# Sheet1.net
KiCad netlist of a schematic drawn in Altium Designer
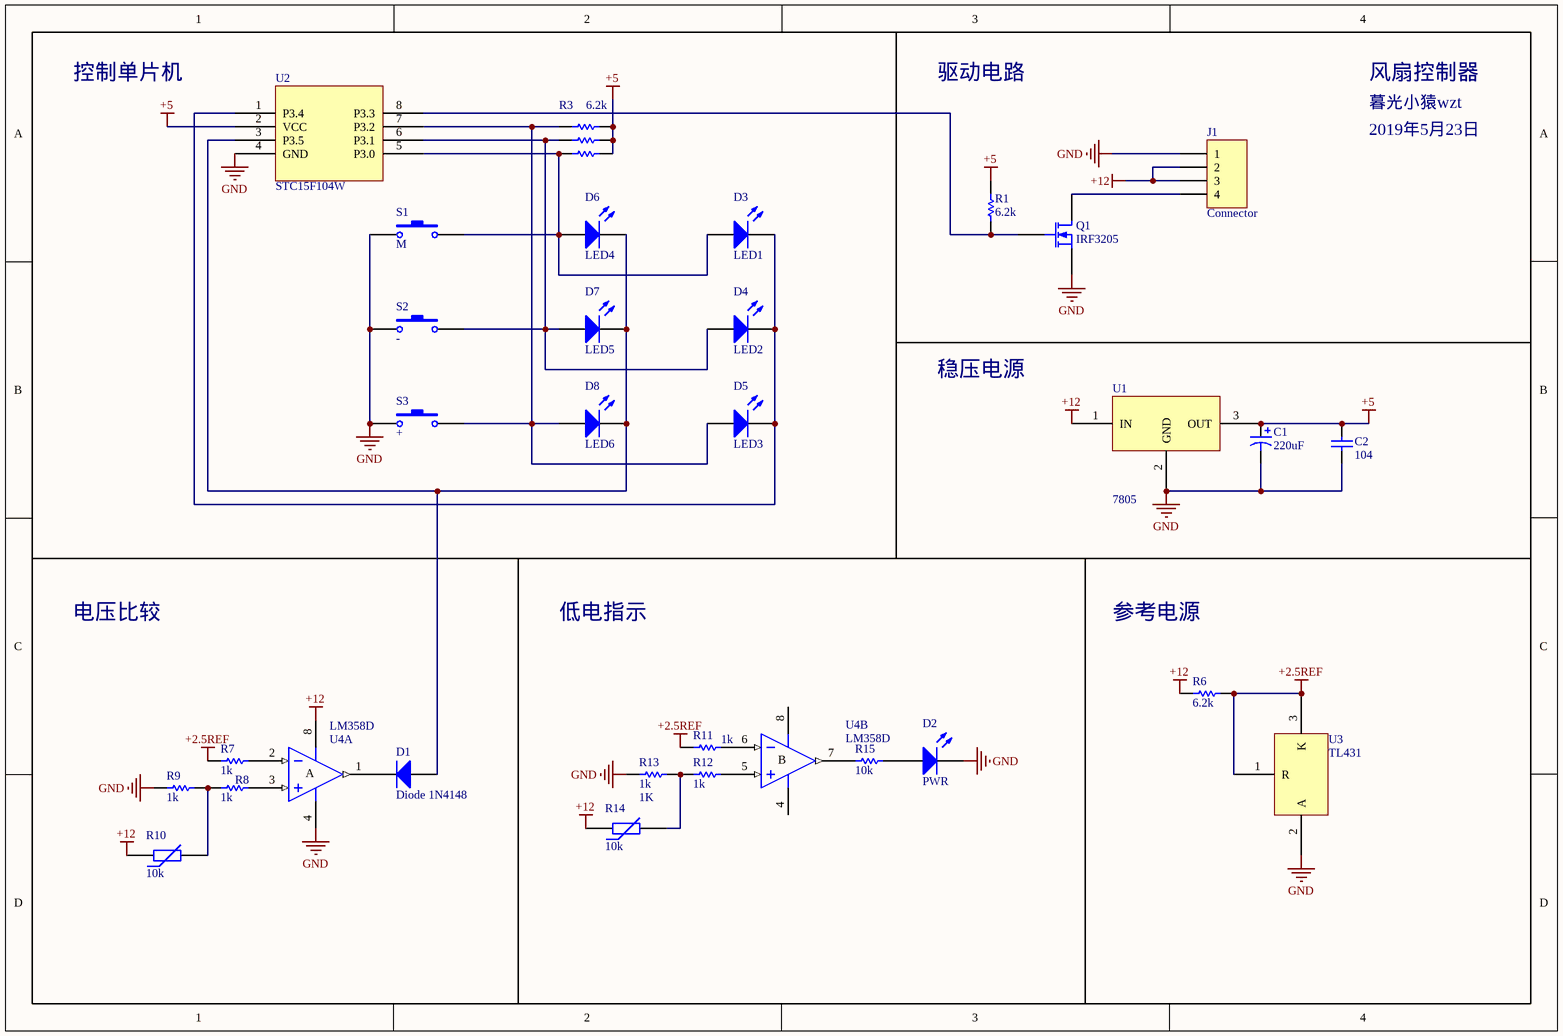
[diagram p0: Sheet1.SchDoc]

(export (version "E")
  (design (tool "Eeschema 10.0.6"))
  (components
    (comp (ref "C1")
      (value "220uF")
      (footprint "RB7.6-15")
      (description "Polarized Capacitor (Radial)")
      (fields (field (name "PUBLISHER") "Altium Limited"))
      (libsource (lib "Miscellaneous Devices") (part "Cap Pol1"))
    )
    (comp (ref "C2")
      (value "104")
      (footprint "RAD-0.3")
      (description "Capacitor")
      (fields (field (name "PUBLISHER") "Altium Limited"))
      (libsource (lib "Miscellaneous Devices") (part "Cap"))
    )
    (comp (ref "D1")
      (value "Diode 1N4148")
      (footprint "DO-35")
      (description "High Conductance Fast Diode")
      (fields (field (name "PUBLISHER") "Altium Limited"))
      (libsource (lib "Miscellaneous Devices") (part "Diode 1N4148"))
    )
    (comp (ref "D2")
      (value "PWR")
      (footprint "LED-0")
      (description "Typical INFRARED GaAs LED")
      (fields (field (name "PUBLISHER") "Altium Limited"))
      (libsource (lib "Miscellaneous Devices") (part "LED0"))
    )
    (comp (ref "D3")
      (value "LED1")
      (footprint "LED-0")
      (description "Typical INFRARED GaAs LED")
      (fields (field (name "PUBLISHER") "Altium Limited"))
      (libsource (lib "Miscellaneous Devices") (part "LED0"))
    )
    (comp (ref "D4")
      (value "LED2")
      (footprint "LED-0")
      (description "Typical INFRARED GaAs LED")
      (fields (field (name "PUBLISHER") "Altium Limited"))
      (libsource (lib "Miscellaneous Devices") (part "LED0"))
    )
    (comp (ref "D5")
      (value "LED3")
      (footprint "LED-0")
      (description "Typical INFRARED GaAs LED")
      (fields (field (name "PUBLISHER") "Altium Limited"))
      (libsource (lib "Miscellaneous Devices") (part "LED0"))
    )
    (comp (ref "D6")
      (value "LED4")
      (footprint "LED-0")
      (description "Typical INFRARED GaAs LED")
      (fields (field (name "PUBLISHER") "Altium Limited"))
      (libsource (lib "Miscellaneous Devices") (part "LED0"))
    )
    (comp (ref "D7")
      (value "LED5")
      (footprint "LED-0")
      (description "Typical INFRARED GaAs LED")
      (fields (field (name "PUBLISHER") "Altium Limited"))
      (libsource (lib "Miscellaneous Devices") (part "LED0"))
    )
    (comp (ref "D8")
      (value "LED6")
      (footprint "LED-0")
      (description "Typical INFRARED GaAs LED")
      (fields (field (name "PUBLISHER") "Altium Limited"))
      (libsource (lib "Miscellaneous Devices") (part "LED0"))
    )
    (comp (ref "J1")
      (value "Connector")
      (footprint "HDR1X4")
      (description "Header, 4-Pin")
      (fields (field (name "PUBLISHER") "Altium Limited"))
      (libsource (lib "Miscellaneous Connectors") (part "Header 4"))
    )
    (comp (ref "Q1")
      (value "IRF3205")
      (footprint "E3")
      (description "N-Channel MOSFET")
      (fields (field (name "PUBLISHER") "Altium Limited"))
      (libsource (lib "Miscellaneous Devices") (part "MOSFET-N"))
    )
    (comp (ref "R1")
      (value "6.2k")
      (footprint "AXIAL-0.3")
      (description "Resistor")
      (fields (field (name "PUBLISHER") "Altium Limited"))
      (libsource (lib "Miscellaneous Devices") (part "Res1"))
    )
    (comp (ref "R3")
      (value "6.2k")
      (footprint "AXIAL-0.3")
      (description "Resistor")
      (fields (field (name "PUBLISHER") "Altium Limited"))
      (libsource (lib "Miscellaneous Devices") (part "Res1"))
    )
    (comp (ref "R4")
      (value "6.2k")
      (footprint "AXIAL-0.3")
      (description "Resistor")
      (fields (field (name "PUBLISHER") "Altium Limited"))
      (libsource (lib "Miscellaneous Devices") (part "Res1"))
    )
    (comp (ref "R5")
      (value "6.2k")
      (footprint "AXIAL-0.3")
      (description "Resistor")
      (fields (field (name "PUBLISHER") "Altium Limited"))
      (libsource (lib "Miscellaneous Devices") (part "Res1"))
    )
    (comp (ref "R6")
      (value "6.2k")
      (footprint "AXIAL-0.3")
      (description "Resistor")
      (fields (field (name "PUBLISHER") "Altium Limited"))
      (libsource (lib "Miscellaneous Devices") (part "Res1"))
    )
    (comp (ref "R7")
      (value "1k")
      (footprint "AXIAL-0.3")
      (description "Resistor")
      (fields (field (name "PUBLISHER") "Altium Limited"))
      (libsource (lib "Miscellaneous Devices") (part "Res1"))
    )
    (comp (ref "R8")
      (value "1k")
      (footprint "AXIAL-0.3")
      (description "Resistor")
      (fields (field (name "PUBLISHER") "Altium Limited"))
      (libsource (lib "Miscellaneous Devices") (part "Res1"))
    )
    (comp (ref "R9")
      (value "1k")
      (footprint "AXIAL-0.3")
      (description "Resistor")
      (fields (field (name "PUBLISHER") "Altium Limited"))
      (libsource (lib "Miscellaneous Devices") (part "Res1"))
    )
    (comp (ref "R10")
      (value "10k")
      (footprint "6-0805_N")
      (description "Varistor (Voltage-Sensitive Resistor)")
      (fields (field (name "PUBLISHER") "Altium Limited"))
      (libsource (lib "Miscellaneous Devices") (part "Res Varistor"))
    )
    (comp (ref "R11")
      (value "1k")
      (footprint "AXIAL-0.3")
      (description "Resistor")
      (fields (field (name "PUBLISHER") "Altium Limited"))
      (libsource (lib "Miscellaneous Devices") (part "Res1"))
    )
    (comp (ref "R12")
      (value "1k")
      (footprint "AXIAL-0.3")
      (description "Resistor")
      (fields (field (name "PUBLISHER") "Altium Limited"))
      (libsource (lib "Miscellaneous Devices") (part "Res1"))
    )
    (comp (ref "R13")
      (value "1k")
      (footprint "AXIAL-0.3")
      (description "Resistor")
      (fields (field (name "ALTIUM_VALUE") "1K") (field (name "PUBLISHER") "Altium Limited"))
      (libsource (lib "Miscellaneous Devices") (part "Res1"))
    )
    (comp (ref "R14")
      (value "10k")
      (footprint "6-0805_N")
      (description "Varistor (Voltage-Sensitive Resistor)")
      (fields (field (name "PUBLISHER") "Altium Limited"))
      (libsource (lib "Miscellaneous Devices") (part "Res Varistor"))
    )
    (comp (ref "R15")
      (value "10k")
      (footprint "AXIAL-0.3")
      (description "Resistor")
      (fields (field (name "PUBLISHER") "Altium Limited"))
      (libsource (lib "Miscellaneous Devices") (part "Res1"))
    )
    (comp (ref "S1")
      (value "M")
      (footprint "SPST-2")
      (description "Switch")
      (fields (field (name "PUBLISHER") "Altium Limited"))
      (libsource (lib "Miscellaneous Devices") (part "SW-PB"))
    )
    (comp (ref "S2")
      (value "-")
      (footprint "SPST-2")
      (description "Switch")
      (fields (field (name "PUBLISHER") "Altium Limited"))
      (libsource (lib "Miscellaneous Devices") (part "SW-PB"))
    )
    (comp (ref "S3")
      (value "+")
      (footprint "SPST-2")
      (description "Switch")
      (fields (field (name "PUBLISHER") "Altium Limited"))
      (libsource (lib "Miscellaneous Devices") (part "SW-PB"))
    )
    (comp (ref "U1") (value "7805") (libsource (lib "Schlib1") (part "7805")))
    (comp (ref "U2") (value "STC15F104W") (libsource (lib "Schlib1") (part "STC15F104W")))
    (comp (ref "U3") (value "TL431") (libsource (lib "Schlib1") (part "TL431")))
    (comp (ref "U4")
      (value "LM358D")
      (footprint "D008_L")
      (description "Dual Operational Amplifier")
      (fields (field (name "PUBLISHER") "Altium Limited"))
      (libsource (lib "TI Operational Amplifier") (part "LM358D"))
    )
  )
  (nets
    (net (code "1") (name "+2.5REF") (class "Default")
      (node (ref "R11") (pin "1") (pinfunction "1_1") (pintype "passive"))
      (node (ref "R6") (pin "2") (pinfunction "2_2") (pintype "passive"))
      (node (ref "R7") (pin "1") (pinfunction "1_1") (pintype "passive"))
      (node (ref "U3") (pin "1") (pinfunction "R_1") (pintype "passive"))
      (node (ref "U3") (pin "3") (pinfunction "K_3") (pintype "passive"))
    )
    (net (code "2") (name "+5") (class "Default")
      (node (ref "C1") (pin "1") (pinfunction "1_1") (pintype "passive"))
      (node (ref "C2") (pin "2") (pinfunction "2_2") (pintype "passive"))
      (node (ref "R1") (pin "2") (pinfunction "2_2") (pintype "passive"))
      (node (ref "R3") (pin "2") (pinfunction "2_2") (pintype "passive"))
      (node (ref "R4") (pin "2") (pinfunction "2_2") (pintype "passive"))
      (node (ref "R5") (pin "2") (pinfunction "2_2") (pintype "passive"))
      (node (ref "U1") (pin "3") (pinfunction "OUT_3") (pintype "passive"))
      (node (ref "U2") (pin "2") (pinfunction "VCC_2") (pintype "passive"))
    )
    (net (code "3") (name "+12") (class "Default")
      (node (ref "J1") (pin "2") (pinfunction "2_2") (pintype "passive"))
      (node (ref "J1") (pin "3") (pinfunction "3_3") (pintype "passive"))
      (node (ref "R10") (pin "1") (pinfunction "1_1") (pintype "passive"))
      (node (ref "R14") (pin "1") (pinfunction "1_1") (pintype "passive"))
      (node (ref "R6") (pin "1") (pinfunction "1_1") (pintype "passive"))
      (node (ref "U1") (pin "1") (pinfunction "IN_1") (pintype "passive"))
      (node (ref "U4") (pin "8") (pinfunction "V+_8") (pintype "power_in"))
    )
    (net (code "4") (name "GND") (class "Default")
      (node (ref "C1") (pin "2") (pinfunction "2_2") (pintype "passive"))
      (node (ref "C2") (pin "1") (pinfunction "1_1") (pintype "passive"))
      (node (ref "D2") (pin "2") (pinfunction "K_2") (pintype "passive"))
      (node (ref "J1") (pin "1") (pinfunction "1_1") (pintype "passive"))
      (node (ref "Q1") (pin "3") (pinfunction "S_3") (pintype "passive"))
      (node (ref "R13") (pin "1") (pinfunction "1_1") (pintype "passive"))
      (node (ref "R9") (pin "1") (pinfunction "1_1") (pintype "passive"))
      (node (ref "S1") (pin "1") (pinfunction "1_1") (pintype "passive"))
      (node (ref "S2") (pin "1") (pinfunction "1_1") (pintype "passive"))
      (node (ref "S3") (pin "1") (pinfunction "1_1") (pintype "passive"))
      (node (ref "U1") (pin "2") (pinfunction "GND_2") (pintype "passive"))
      (node (ref "U2") (pin "4") (pinfunction "GND_4") (pintype "passive"))
      (node (ref "U3") (pin "2") (pinfunction "A_2") (pintype "passive"))
      (node (ref "U4") (pin "4") (pinfunction "V-_4") (pintype "power_in"))
    )
    (net (code "5") (name "Net-(D1-A)") (class "Default")
      (node (ref "D1") (pin "1") (pinfunction "A_1") (pintype "passive"))
      (node (ref "D6") (pin "2") (pinfunction "K_2") (pintype "passive"))
      (node (ref "D7") (pin "2") (pinfunction "K_2") (pintype "passive"))
      (node (ref "D8") (pin "2") (pinfunction "K_2") (pintype "passive"))
      (node (ref "U2") (pin "3") (pinfunction "P3.5_3") (pintype "passive"))
    )
    (net (code "6") (name "Net-(D1-K)") (class "Default")
      (node (ref "D1") (pin "2") (pinfunction "K_2") (pintype "passive"))
      (node (ref "U4") (pin "1") (pinfunction "OUT_1") (pintype "output"))
    )
    (net (code "7") (name "Net-(D2-A)") (class "Default")
      (node (ref "D2") (pin "1") (pinfunction "A_1") (pintype "passive"))
      (node (ref "R15") (pin "2") (pinfunction "2_2") (pintype "passive"))
    )
    (net (code "8") (name "Net-(D3-A)") (class "Default")
      (node (ref "D3") (pin "1") (pinfunction "A_1") (pintype "passive"))
      (node (ref "D6") (pin "1") (pinfunction "A_1") (pintype "passive"))
      (node (ref "R5") (pin "1") (pinfunction "1_1") (pintype "passive"))
      (node (ref "S1") (pin "2") (pinfunction "2_2") (pintype "passive"))
      (node (ref "U2") (pin "5") (pinfunction "P3.0_5") (pintype "passive"))
    )
    (net (code "9") (name "Net-(D3-K)") (class "Default")
      (node (ref "D3") (pin "2") (pinfunction "K_2") (pintype "passive"))
      (node (ref "D4") (pin "2") (pinfunction "K_2") (pintype "passive"))
      (node (ref "D5") (pin "2") (pinfunction "K_2") (pintype "passive"))
      (node (ref "U2") (pin "1") (pinfunction "P3.4_1") (pintype "passive"))
    )
    (net (code "10") (name "Net-(D4-A)") (class "Default")
      (node (ref "D4") (pin "1") (pinfunction "A_1") (pintype "passive"))
      (node (ref "D7") (pin "1") (pinfunction "A_1") (pintype "passive"))
      (node (ref "R4") (pin "1") (pinfunction "1_1") (pintype "passive"))
      (node (ref "S2") (pin "2") (pinfunction "2_2") (pintype "passive"))
      (node (ref "U2") (pin "6") (pinfunction "P3.1_6") (pintype "passive"))
    )
    (net (code "11") (name "Net-(D5-A)") (class "Default")
      (node (ref "D5") (pin "1") (pinfunction "A_1") (pintype "passive"))
      (node (ref "D8") (pin "1") (pinfunction "A_1") (pintype "passive"))
      (node (ref "R3") (pin "1") (pinfunction "1_1") (pintype "passive"))
      (node (ref "S3") (pin "2") (pinfunction "2_2") (pintype "passive"))
      (node (ref "U2") (pin "7") (pinfunction "P3.2_7") (pintype "passive"))
    )
    (net (code "12") (name "Net-(Q1-D)") (class "Default")
      (node (ref "J1") (pin "4") (pinfunction "4_4") (pintype "passive"))
      (node (ref "Q1") (pin "1") (pinfunction "D_1") (pintype "passive"))
    )
    (net (code "13") (name "Net-(Q1-G)") (class "Default")
      (node (ref "Q1") (pin "2") (pinfunction "G_2") (pintype "passive"))
      (node (ref "R1") (pin "1") (pinfunction "1_1") (pintype "passive"))
      (node (ref "U2") (pin "8") (pinfunction "P3.3_8") (pintype "passive"))
    )
    (net (code "14") (name "Net-(R10-Pad2)") (class "Default")
      (node (ref "R10") (pin "2") (pinfunction "2_2") (pintype "passive"))
      (node (ref "R8") (pin "1") (pinfunction "1_1") (pintype "passive"))
      (node (ref "R9") (pin "2") (pinfunction "2_2") (pintype "passive"))
    )
    (net (code "15") (name "Net-(R12-Pad1)") (class "Default")
      (node (ref "R12") (pin "1") (pinfunction "1_1") (pintype "passive"))
      (node (ref "R13") (pin "2") (pinfunction "2_2") (pintype "passive"))
      (node (ref "R14") (pin "2") (pinfunction "2_2") (pintype "passive"))
    )
    (net (code "16") (name "Net-(U4A-IN+)") (class "Default")
      (node (ref "R8") (pin "2") (pinfunction "2_2") (pintype "passive"))
      (node (ref "U4") (pin "3") (pinfunction "IN+_3") (pintype "input"))
    )
    (net (code "17") (name "Net-(U4A-IN-)") (class "Default")
      (node (ref "R7") (pin "2") (pinfunction "2_2") (pintype "passive"))
      (node (ref "U4") (pin "2") (pinfunction "IN-_2") (pintype "input"))
    )
    (net (code "18") (name "Net-(U4B-IN+)") (class "Default")
      (node (ref "R12") (pin "2") (pinfunction "2_2") (pintype "passive"))
      (node (ref "U4") (pin "5") (pinfunction "IN+_5") (pintype "input"))
    )
    (net (code "19") (name "Net-(U4B-IN-)") (class "Default")
      (node (ref "R11") (pin "2") (pinfunction "2_2") (pintype "passive"))
      (node (ref "U4") (pin "6") (pinfunction "IN-_6") (pintype "input"))
    )
    (net (code "20") (name "Net-(U4B-OUT)") (class "Default")
      (node (ref "R15") (pin "1") (pinfunction "1_1") (pintype "passive"))
      (node (ref "U4") (pin "7") (pinfunction "OUT_7") (pintype "output"))
    )
    (net (code "21") (name "unconnected-(U4B-V+-Pad8)") (class "Default")
      (node (ref "U4") (pin "8") (pinfunction "V+_8") (pintype "power_in"))
    )
    (net (code "22") (name "unconnected-(U4B-V--Pad4)") (class "Default")
      (node (ref "U4") (pin "4") (pinfunction "V-_4") (pintype "power_in"))
    )
  )
)
